# miniDAC.net
KiCad netlist of a schematic drawn in EAGLE
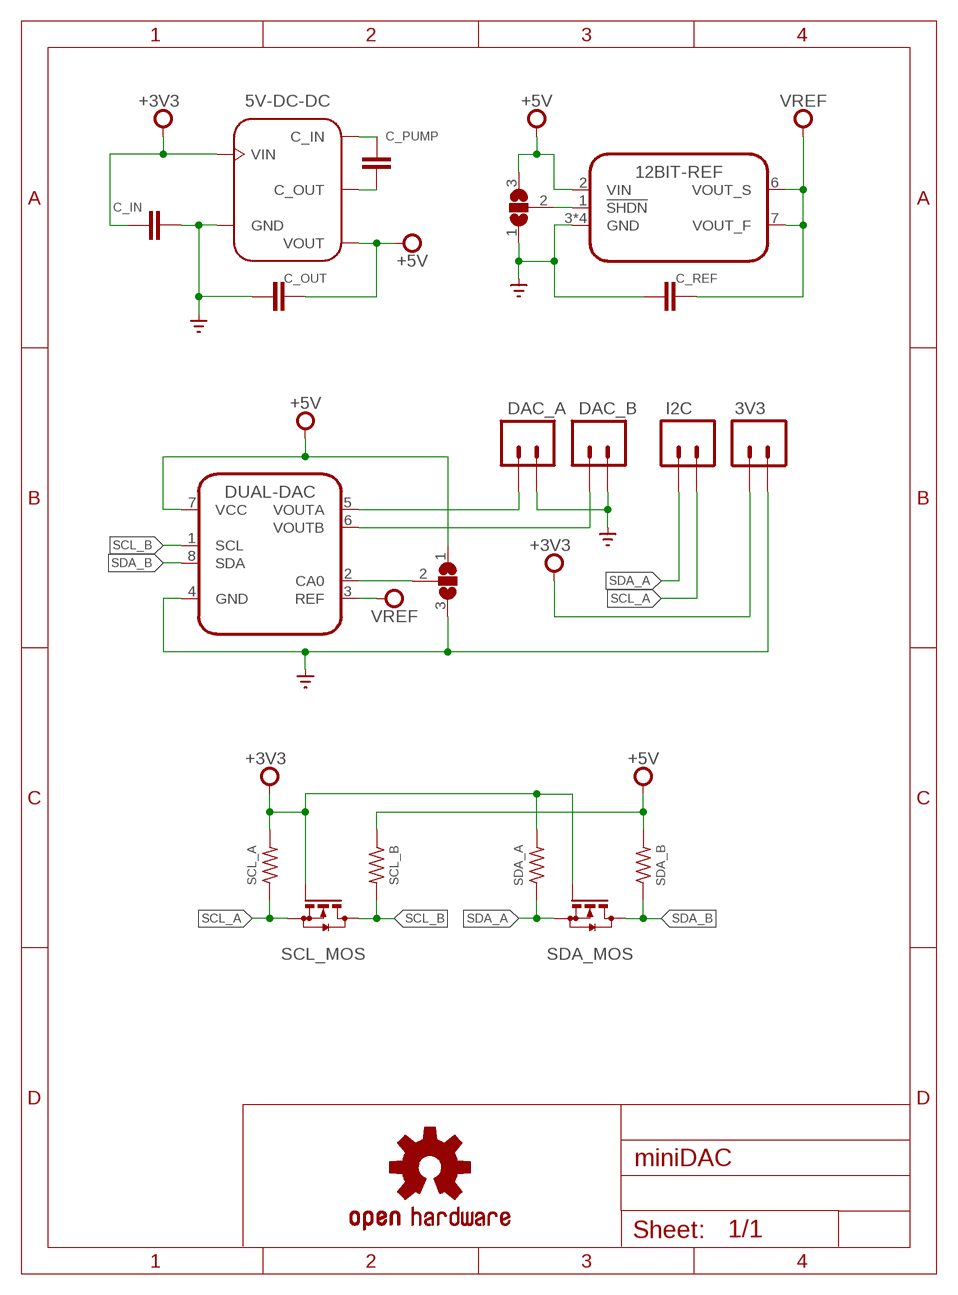
[diagram p0: schematic, sheet 1]

(export (version "E")
  (design (tool "Eeschema 10.0.6"))
  (components
    (comp (ref "3V3")
      (value "M02LOCK")
      (footprint "eagle-import:1X02_LOCK")
      (libsource (lib "eagle-import") (part "M02LOCK"))
    )
    (comp (ref "5V-DC-DC")
      (value "LTC1517CS5-5#PBF")
      (footprint "eagle-import:SOT-23_S5")
      (libsource (lib "eagle-import") (part "LTC1517CS5-5#PBF"))
    )
    (comp (ref "12BIT-REF")
      (value "LTC6655CHMS8-5PBF")
      (footprint "eagle-import:SOP65P490X110-8N")
      (fields (field (name "MF") "Linear Technology") (field (name "MP") "LTC6655CHMS8-5#PBF"))
      (libsource (lib "eagle-import") (part "LTC6655CHMS8-5PBF"))
    )
    (comp (ref "ADDR_SEL")
      (value "SJ2WW")
      (footprint "eagle-import:SJ_2W")
      (libsource (lib "eagle-import") (part "SJ2WW"))
    )
    (comp (ref "C_IN")
      (value "3.3uF")
      (footprint "eagle-import:C1206K")
      (libsource (lib "eagle-import") (part "C-EUC1206K"))
    )
    (comp (ref "C_OUT")
      (value "6.8uF")
      (footprint "eagle-import:C1206K")
      (libsource (lib "eagle-import") (part "C-EUC1206K"))
    )
    (comp (ref "C_PUMP")
      (value "0.1uF")
      (footprint "eagle-import:C1206K")
      (libsource (lib "eagle-import") (part "C-EUC1206K"))
    )
    (comp (ref "C_REF")
      (value "10uF")
      (footprint "eagle-import:C1206K")
      (libsource (lib "eagle-import") (part "C-EUC1206K"))
    )
    (comp (ref "DAC_A")
      (value "M025MM")
      (footprint "eagle-import:SCREWTERMINAL-5MM-2")
      (libsource (lib "eagle-import") (part "M025MM"))
    )
    (comp (ref "DAC_B")
      (value "M025MM")
      (footprint "eagle-import:SCREWTERMINAL-5MM-2")
      (libsource (lib "eagle-import") (part "M025MM"))
    )
    (comp (ref "DUAL-DAC")
      (value "LTC2633CTS8-HZ8PBF")
      (footprint "eagle-import:SOT65P280X100-8N")
      (fields (field (name "MF") "Linear Technology") (field (name "MP") "LTC2633CTS8-HZ8#PBF"))
      (libsource (lib "eagle-import") (part "LTC2633CTS8-HZ8PBF"))
    )
    (comp (ref "I2C")
      (value "M02LOCK")
      (footprint "eagle-import:1X02_LOCK")
      (libsource (lib "eagle-import") (part "M02LOCK"))
    )
    (comp (ref "OSHW")
      (value "OSHW-LOGOL")
      (footprint "eagle-import:OSHW-LOGO-L")
      (libsource (lib "eagle-import") (part "OSHW-LOGOL"))
    )
    (comp (ref "REF_SEL")
      (value "SJ2WW")
      (footprint "eagle-import:SJ_2W")
      (libsource (lib "eagle-import") (part "SJ2WW"))
    )
    (comp (ref "SCL_A")
      (value "2.7K")
      (footprint "eagle-import:M1206")
      (libsource (lib "eagle-import") (part "R-US_M1206"))
    )
    (comp (ref "SCL_B")
      (value "1.3K")
      (footprint "eagle-import:M1206")
      (libsource (lib "eagle-import") (part "R-US_M1206"))
    )
    (comp (ref "SCL_MOS")
      (value "BSS123")
      (footprint "eagle-import:SOT23")
      (libsource (lib "eagle-import") (part "BSS123"))
    )
    (comp (ref "SDA_A")
      (value "2.7K")
      (footprint "eagle-import:M1206")
      (libsource (lib "eagle-import") (part "R-US_M1206"))
    )
    (comp (ref "SDA_B")
      (value "1.3K")
      (footprint "eagle-import:M1206")
      (libsource (lib "eagle-import") (part "R-US_M1206"))
    )
    (comp (ref "SDA_MOS")
      (value "BSS123")
      (footprint "eagle-import:SOT23")
      (libsource (lib "eagle-import") (part "BSS123"))
    )
  )
  (nets
    (net (code "1") (name "+3V3") (class "Default")
      (node (ref "3V3") (pin "1") (pinfunction "1_1") (pintype "passive"))
      (node (ref "5V-DC-DC") (pin "VIN") (pinfunction "VIN_VIN") (pintype "input"))
      (node (ref "C_IN") (pin "1") (pinfunction "1_1") (pintype "passive"))
      (node (ref "SCL_A") (pin "2") (pinfunction "2_2") (pintype "passive"))
      (node (ref "SCL_MOS") (pin "1") (pinfunction "G_1") (pintype "passive"))
      (node (ref "SDA_A") (pin "2") (pinfunction "2_2") (pintype "passive"))
      (node (ref "SDA_MOS") (pin "1") (pinfunction "G_1") (pintype "passive"))
    )
    (net (code "2") (name "+5V") (class "Default")
      (node (ref "12BIT-REF") (pin "2") (pinfunction "VIN_2") (pintype "power_in"))
      (node (ref "5V-DC-DC") (pin "VOUT") (pinfunction "VOUT_VOUT") (pintype "output"))
      (node (ref "ADDR_SEL") (pin "1") (pinfunction "1_1") (pintype "passive"))
      (node (ref "C_OUT") (pin "2") (pinfunction "2_2") (pintype "passive"))
      (node (ref "DUAL-DAC") (pin "7") (pinfunction "VCC_7") (pintype "power_in"))
      (node (ref "REF_SEL") (pin "3") (pinfunction "3_3") (pintype "passive"))
      (node (ref "SCL_B") (pin "1") (pinfunction "1_1") (pintype "passive"))
      (node (ref "SDA_B") (pin "2") (pinfunction "2_2") (pintype "passive"))
    )
    (net (code "3") (name "GND") (class "Default")
      (node (ref "12BIT-REF") (pin "3") (pinfunction "GND_3") (pintype "power_in"))
      (node (ref "12BIT-REF") (pin "4") (pinfunction "GND_4") (pintype "power_in"))
      (node (ref "12BIT-REF") (pin "5") (pinfunction "GND_5") (pintype "power_in"))
      (node (ref "12BIT-REF") (pin "8") (pinfunction "GND_8") (pintype "power_in"))
      (node (ref "3V3") (pin "2") (pinfunction "2_2") (pintype "passive"))
      (node (ref "5V-DC-DC") (pin "GND") (pinfunction "GND_GND") (pintype "power_in"))
      (node (ref "ADDR_SEL") (pin "3") (pinfunction "3_3") (pintype "passive"))
      (node (ref "C_IN") (pin "2") (pinfunction "2_2") (pintype "passive"))
      (node (ref "C_OUT") (pin "1") (pinfunction "1_1") (pintype "passive"))
      (node (ref "C_REF") (pin "2") (pinfunction "2_2") (pintype "passive"))
      (node (ref "DAC_A") (pin "1") (pinfunction "1_1") (pintype "passive"))
      (node (ref "DAC_B") (pin "1") (pinfunction "1_1") (pintype "passive"))
      (node (ref "DUAL-DAC") (pin "4") (pinfunction "GND_4") (pintype "passive"))
      (node (ref "REF_SEL") (pin "1") (pinfunction "1_1") (pintype "passive"))
    )
    (net (code "4") (name "Net-(5V-DC-DC-C_IN)") (class "Default")
      (node (ref "5V-DC-DC") (pin "C_OUT") (pinfunction "C_IN_C_OUT") (pintype "bidirectional"))
      (node (ref "C_PUMP") (pin "1") (pinfunction "1_1") (pintype "passive"))
    )
    (net (code "5") (name "Net-(5V-DC-DC-C_OUT)") (class "Default")
      (node (ref "5V-DC-DC") (pin "C_IN") (pinfunction "C_OUT_C_IN") (pintype "bidirectional"))
      (node (ref "C_PUMP") (pin "2") (pinfunction "2_2") (pintype "passive"))
    )
    (net (code "6") (name "Net-(12BIT-REF-~{SHDN})") (class "Default")
      (node (ref "12BIT-REF") (pin "1") (pinfunction "~{SHDN}_1") (pintype "input"))
      (node (ref "REF_SEL") (pin "2") (pinfunction "2_2") (pintype "passive"))
    )
    (net (code "7") (name "Net-(DUAL-DAC-CA0)") (class "Default")
      (node (ref "ADDR_SEL") (pin "2") (pinfunction "2_2") (pintype "passive"))
      (node (ref "DUAL-DAC") (pin "2") (pinfunction "CA0_2") (pintype "input"))
    )
    (net (code "8") (name "Net-(DUAL-DAC-VOUTA)") (class "Default")
      (node (ref "DAC_A") (pin "2") (pinfunction "2_2") (pintype "passive"))
      (node (ref "DUAL-DAC") (pin "5") (pinfunction "VOUTA_5") (pintype "output"))
    )
    (net (code "9") (name "Net-(DUAL-DAC-VOUTB)") (class "Default")
      (node (ref "DAC_B") (pin "2") (pinfunction "2_2") (pintype "passive"))
      (node (ref "DUAL-DAC") (pin "6") (pinfunction "VOUTB_6") (pintype "output"))
    )
    (net (code "10") (name "SCL_A") (class "Default")
      (node (ref "I2C") (pin "2") (pinfunction "2_2") (pintype "passive"))
      (node (ref "SCL_A") (pin "1") (pinfunction "1_1") (pintype "passive"))
      (node (ref "SCL_MOS") (pin "2") (pinfunction "S_2") (pintype "passive"))
    )
    (net (code "11") (name "SCL_B") (class "Default")
      (node (ref "DUAL-DAC") (pin "1") (pinfunction "SCL_1") (pintype "input"))
      (node (ref "SCL_B") (pin "2") (pinfunction "2_2") (pintype "passive"))
      (node (ref "SCL_MOS") (pin "3") (pinfunction "D_3") (pintype "passive"))
    )
    (net (code "12") (name "SDA_A") (class "Default")
      (node (ref "I2C") (pin "1") (pinfunction "1_1") (pintype "passive"))
      (node (ref "SDA_A") (pin "1") (pinfunction "1_1") (pintype "passive"))
      (node (ref "SDA_MOS") (pin "2") (pinfunction "S_2") (pintype "passive"))
    )
    (net (code "13") (name "SDA_B") (class "Default")
      (node (ref "DUAL-DAC") (pin "8") (pinfunction "SDA_8") (pintype "bidirectional"))
      (node (ref "SDA_B") (pin "1") (pinfunction "1_1") (pintype "passive"))
      (node (ref "SDA_MOS") (pin "3") (pinfunction "D_3") (pintype "passive"))
    )
    (net (code "14") (name "VREF") (class "Default")
      (node (ref "12BIT-REF") (pin "6") (pinfunction "VOUT_S_6") (pintype "output"))
      (node (ref "12BIT-REF") (pin "7") (pinfunction "VOUT_F_7") (pintype "output"))
      (node (ref "C_REF") (pin "1") (pinfunction "1_1") (pintype "passive"))
      (node (ref "DUAL-DAC") (pin "3") (pinfunction "REF_3") (pintype "input"))
    )
  )
)
